# power.net
KiCad netlist of a schematic drawn in Altium Designer
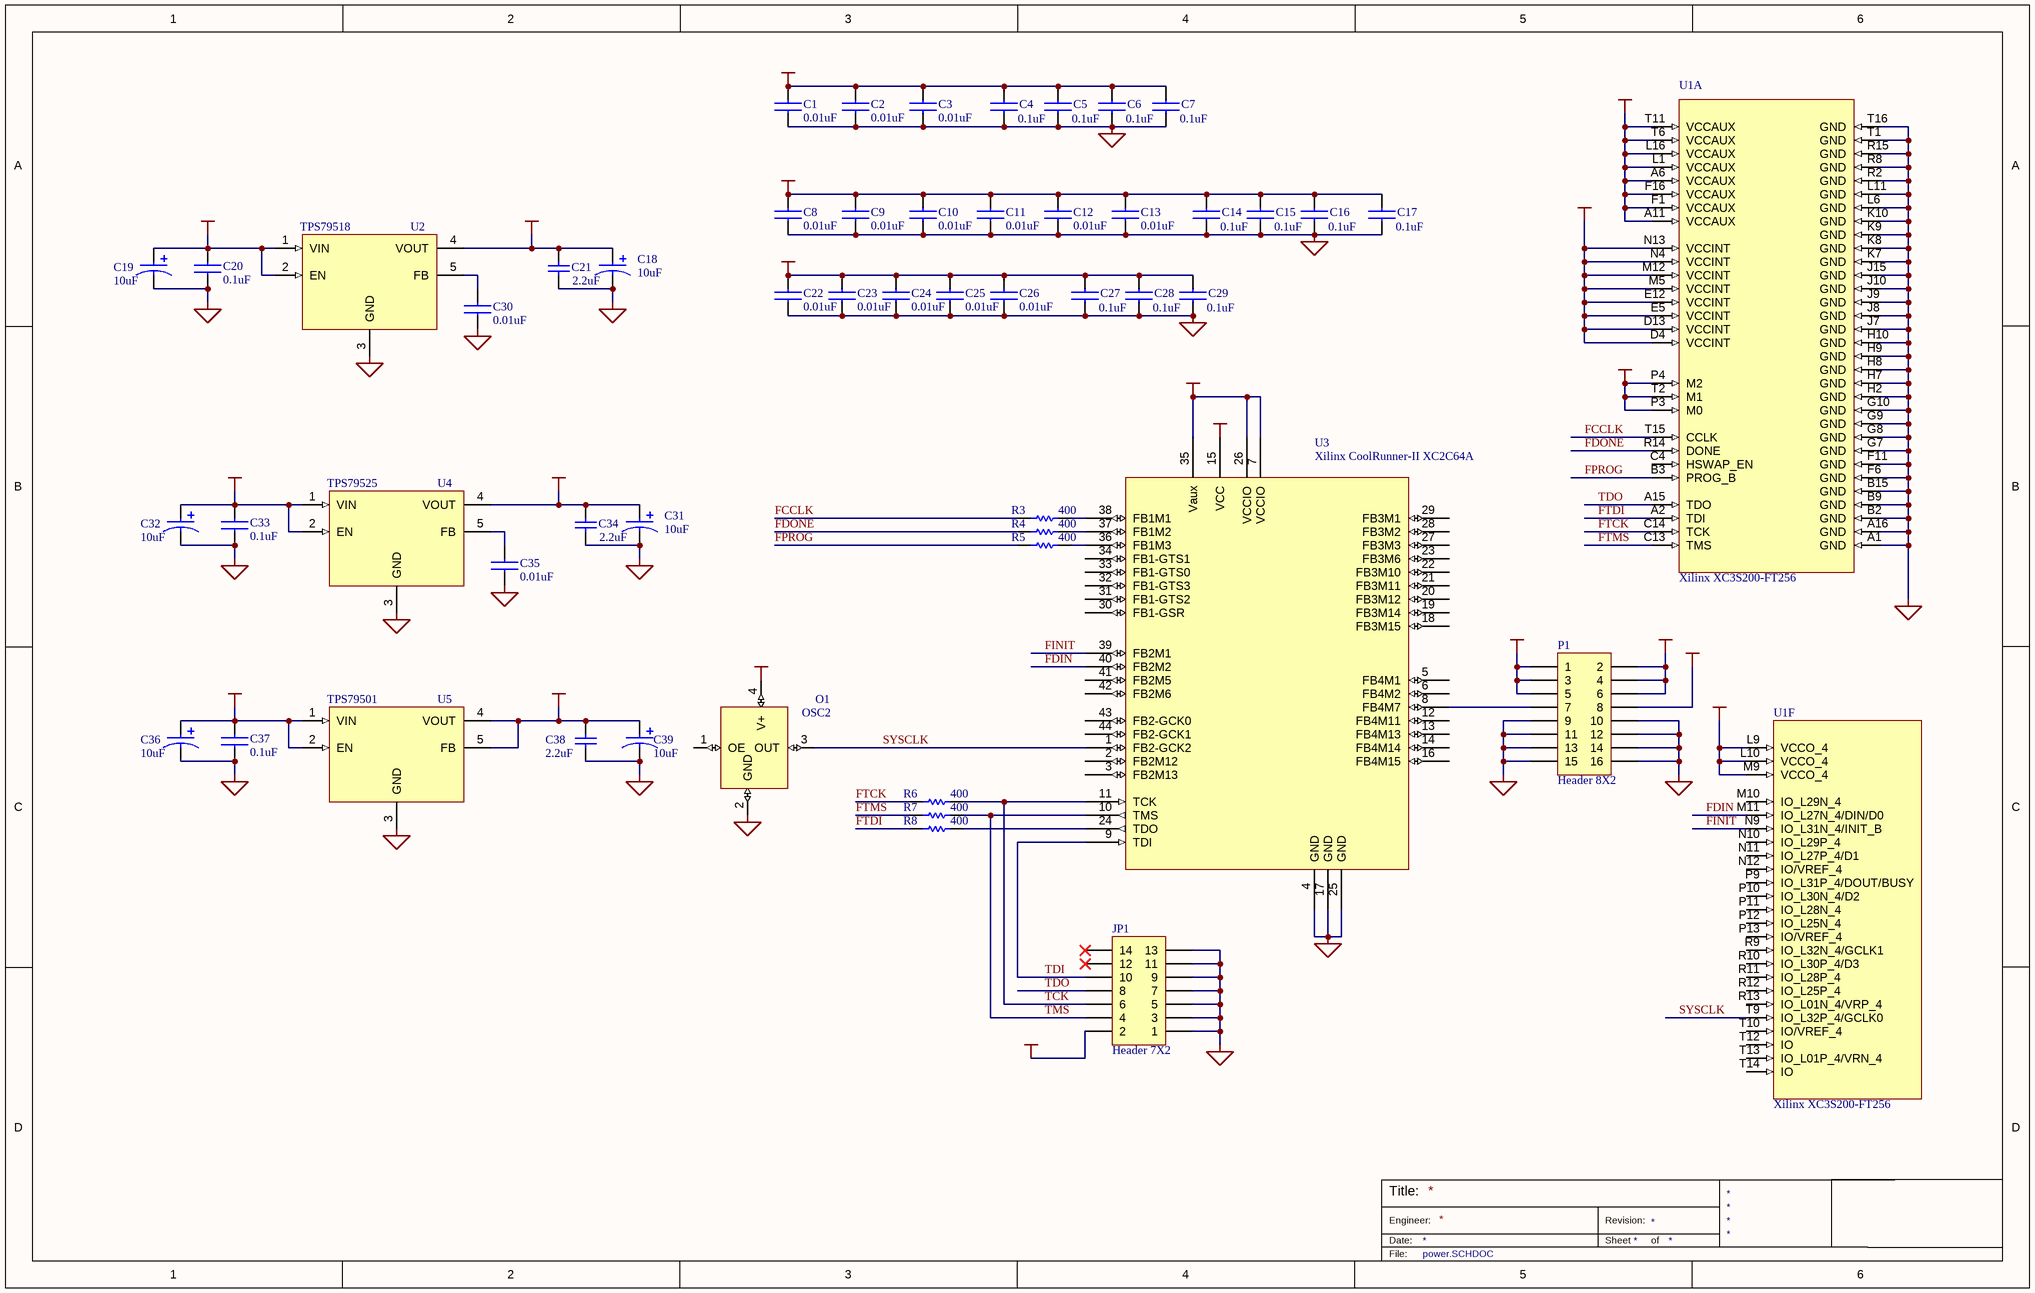
[diagram p0: power.SCHDOC]

(export (version "E")
  (design (tool "Eeschema 10.0.6"))
  (components
    (comp (ref "C1")
      (value "0.01uF")
      (footprint "0402")
      (description "Standard Capacitor")
      (fields (field (name "Comment") "CAPACITOR"))
      (libsource (lib "parts") (part "CAPACITOR"))
    )
    (comp (ref "C2")
      (value "0.01uF")
      (footprint "0402")
      (description "Standard Capacitor")
      (fields (field (name "Comment") "CAPACITOR"))
      (libsource (lib "parts") (part "CAPACITOR"))
    )
    (comp (ref "C3")
      (value "0.01uF")
      (footprint "0402")
      (description "Standard Capacitor")
      (fields (field (name "Comment") "CAPACITOR"))
      (libsource (lib "parts") (part "CAPACITOR"))
    )
    (comp (ref "C4")
      (value "0.1uF")
      (footprint "0603")
      (description "Standard Capacitor")
      (fields (field (name "Comment") "CAPACITOR"))
      (libsource (lib "parts") (part "CAPACITOR"))
    )
    (comp (ref "C5")
      (value "0.1uF")
      (footprint "0603")
      (description "Standard Capacitor")
      (fields (field (name "Comment") "CAPACITOR"))
      (libsource (lib "parts") (part "CAPACITOR"))
    )
    (comp (ref "C6")
      (value "0.1uF")
      (footprint "0603")
      (description "Standard Capacitor")
      (fields (field (name "Comment") "CAPACITOR"))
      (libsource (lib "parts") (part "CAPACITOR"))
    )
    (comp (ref "C7")
      (value "0.1uF")
      (footprint "0603")
      (description "Standard Capacitor")
      (fields (field (name "Comment") "CAPACITOR"))
      (libsource (lib "parts") (part "CAPACITOR"))
    )
    (comp (ref "C8")
      (value "0.01uF")
      (footprint "0402")
      (description "Standard Capacitor")
      (fields (field (name "Comment") "CAPACITOR"))
      (libsource (lib "parts") (part "CAPACITOR"))
    )
    (comp (ref "C9")
      (value "0.01uF")
      (footprint "0402")
      (description "Standard Capacitor")
      (fields (field (name "Comment") "CAPACITOR"))
      (libsource (lib "parts") (part "CAPACITOR"))
    )
    (comp (ref "C10")
      (value "0.01uF")
      (footprint "0402")
      (description "Standard Capacitor")
      (fields (field (name "Comment") "CAPACITOR"))
      (libsource (lib "parts") (part "CAPACITOR"))
    )
    (comp (ref "C11")
      (value "0.01uF")
      (footprint "0402")
      (description "Standard Capacitor")
      (fields (field (name "Comment") "CAPACITOR"))
      (libsource (lib "parts") (part "CAPACITOR"))
    )
    (comp (ref "C12")
      (value "0.01uF")
      (footprint "0402")
      (description "Standard Capacitor")
      (fields (field (name "Comment") "CAPACITOR"))
      (libsource (lib "parts") (part "CAPACITOR"))
    )
    (comp (ref "C13")
      (value "0.01uF")
      (footprint "0402")
      (description "Standard Capacitor")
      (fields (field (name "Comment") "CAPACITOR"))
      (libsource (lib "parts") (part "CAPACITOR"))
    )
    (comp (ref "C14")
      (value "0.1uF")
      (footprint "0603")
      (description "Standard Capacitor")
      (fields (field (name "Comment") "CAPACITOR"))
      (libsource (lib "parts") (part "CAPACITOR"))
    )
    (comp (ref "C15")
      (value "0.1uF")
      (footprint "0603")
      (description "Standard Capacitor")
      (fields (field (name "Comment") "CAPACITOR"))
      (libsource (lib "parts") (part "CAPACITOR"))
    )
    (comp (ref "C16")
      (value "0.1uF")
      (footprint "0603")
      (description "Standard Capacitor")
      (fields (field (name "Comment") "CAPACITOR"))
      (libsource (lib "parts") (part "CAPACITOR"))
    )
    (comp (ref "C17")
      (value "0.1uF")
      (footprint "0603")
      (description "Standard Capacitor")
      (fields (field (name "Comment") "CAPACITOR"))
      (libsource (lib "parts") (part "CAPACITOR"))
    )
    (comp (ref "C18")
      (value "10uF")
      (footprint "6032")
      (description "Standard Capacitor")
      (fields (field (name "Comment") "POLCAP2"))
      (libsource (lib "parts") (part "POLCAP2"))
    )
    (comp (ref "C19")
      (value "10uF")
      (footprint "6032")
      (description "Standard Capacitor")
      (fields (field (name "Comment") "POLCAP2"))
      (libsource (lib "parts") (part "POLCAP2"))
    )
    (comp (ref "C20")
      (value "0.1uF")
      (footprint "0603")
      (description "Standard Capacitor")
      (fields (field (name "Comment") "CAPACITOR"))
      (libsource (lib "parts") (part "CAPACITOR"))
    )
    (comp (ref "C21")
      (value "2.2uF")
      (footprint "1206")
      (description "Capacitor")
      (fields
        (field (name "MANUFACTURER") "Generic Components")
        (field (name "Comment") "Cap")
        (field (name "PUBLISHER") "Altium Limited")
      )
      (libsource (lib "Miscellaneous Devices") (part "Cap"))
    )
    (comp (ref "C22")
      (value "0.01uF")
      (footprint "0402")
      (description "Standard Capacitor")
      (fields (field (name "Comment") "CAPACITOR"))
      (libsource (lib "parts") (part "CAPACITOR"))
    )
    (comp (ref "C23")
      (value "0.01uF")
      (footprint "0402")
      (description "Standard Capacitor")
      (fields (field (name "Comment") "CAPACITOR"))
      (libsource (lib "parts") (part "CAPACITOR"))
    )
    (comp (ref "C24")
      (value "0.01uF")
      (footprint "0402")
      (description "Standard Capacitor")
      (fields (field (name "Comment") "CAPACITOR"))
      (libsource (lib "parts") (part "CAPACITOR"))
    )
    (comp (ref "C25")
      (value "0.01uF")
      (footprint "0402")
      (description "Standard Capacitor")
      (fields (field (name "Comment") "CAPACITOR"))
      (libsource (lib "parts") (part "CAPACITOR"))
    )
    (comp (ref "C26")
      (value "0.01uF")
      (footprint "0402")
      (description "Standard Capacitor")
      (fields (field (name "Comment") "CAPACITOR"))
      (libsource (lib "parts") (part "CAPACITOR"))
    )
    (comp (ref "C27")
      (value "0.1uF")
      (footprint "0603")
      (description "Standard Capacitor")
      (fields (field (name "Comment") "CAPACITOR"))
      (libsource (lib "parts") (part "CAPACITOR"))
    )
    (comp (ref "C28")
      (value "0.1uF")
      (footprint "0603")
      (description "Standard Capacitor")
      (fields (field (name "Comment") "CAPACITOR"))
      (libsource (lib "parts") (part "CAPACITOR"))
    )
    (comp (ref "C29")
      (value "0.1uF")
      (footprint "0603")
      (description "Standard Capacitor")
      (fields (field (name "Comment") "CAPACITOR"))
      (libsource (lib "parts") (part "CAPACITOR"))
    )
    (comp (ref "C30")
      (value "0.01uF")
      (footprint "0402")
      (description "Standard Capacitor")
      (fields (field (name "Comment") "CAPACITOR"))
      (libsource (lib "parts") (part "CAPACITOR"))
    )
    (comp (ref "C31")
      (value "10uF")
      (footprint "6032")
      (description "Standard Capacitor")
      (fields (field (name "Comment") "POLCAP2"))
      (libsource (lib "parts") (part "POLCAP2"))
    )
    (comp (ref "C32")
      (value "10uF")
      (footprint "6032")
      (description "Standard Capacitor")
      (fields (field (name "Comment") "POLCAP2"))
      (libsource (lib "parts") (part "POLCAP2"))
    )
    (comp (ref "C33")
      (value "0.1uF")
      (footprint "0603")
      (description "Standard Capacitor")
      (fields (field (name "Comment") "CAPACITOR"))
      (libsource (lib "parts") (part "CAPACITOR"))
    )
    (comp (ref "C34")
      (value "2.2uF")
      (footprint "1206")
      (description "Capacitor")
      (fields
        (field (name "MANUFACTURER") "Generic Components")
        (field (name "Comment") "Cap")
        (field (name "PUBLISHER") "Altium Limited")
      )
      (libsource (lib "Miscellaneous Devices") (part "Cap"))
    )
    (comp (ref "C35")
      (value "0.01uF")
      (footprint "0402")
      (description "Standard Capacitor")
      (fields (field (name "Comment") "CAPACITOR"))
      (libsource (lib "parts") (part "CAPACITOR"))
    )
    (comp (ref "C36")
      (value "10uF")
      (footprint "6032")
      (description "Standard Capacitor")
      (fields (field (name "Comment") "POLCAP2"))
      (libsource (lib "parts") (part "POLCAP2"))
    )
    (comp (ref "C37")
      (value "0.1uF")
      (footprint "0603")
      (description "Standard Capacitor")
      (fields (field (name "Comment") "CAPACITOR"))
      (libsource (lib "parts") (part "CAPACITOR"))
    )
    (comp (ref "C38")
      (value "2.2uF")
      (footprint "1206")
      (description "Capacitor")
      (fields
        (field (name "MANUFACTURER") "Generic Components")
        (field (name "Comment") "Cap")
        (field (name "PUBLISHER") "Altium Limited")
      )
      (libsource (lib "Miscellaneous Devices") (part "Cap"))
    )
    (comp (ref "C39")
      (value "10uF")
      (footprint "6032")
      (description "Standard Capacitor")
      (fields (field (name "Comment") "POLCAP2"))
      (libsource (lib "parts") (part "POLCAP2"))
    )
    (comp (ref "JP1")
      (value "Header 7X2")
      (footprint "SMT 2x7 2mm HDR")
      (description "Header, 7-Pin, Dual row")
      (fields (field (name "MANUFACTURER") "Generic Components") (field (name "PUBLISHER") "Altium Limited"))
      (libsource (lib "Miscellaneous Connectors") (part "Header 7X2"))
    )
    (comp (ref "O1")
      (value "OSC2")
      (footprint "ECS-3953M")
      (description "ECS SMD Oscillator, ECS-3953M")
      (libsource (lib "parts") (part "OSC2"))
    )
    (comp (ref "P1")
      (value "Header 8X2")
      (footprint "MOLEX 15-91-2160")
      (description "Header, 8-Pin, Dual row")
      (fields (field (name "PUBLISHER") "Altium Limited"))
      (libsource (lib "Miscellaneous Connectors") (part "Header 8X2"))
    )
    (comp (ref "R3")
      (value "400")
      (footprint "CC1608-0603")
      (description "Resistor")
      (fields
        (field (name "MANUFACTURER") "Generic Components")
        (field (name "Comment") "current-limiting series res")
        (field (name "PUBLISHER") "Altium Limited")
      )
      (libsource (lib "Miscellaneous Devices") (part "Res1"))
    )
    (comp (ref "R4")
      (value "400")
      (footprint "CC1608-0603")
      (description "Resistor")
      (fields
        (field (name "MANUFACTURER") "Generic Components")
        (field (name "Comment") "current-limiting series res")
        (field (name "PUBLISHER") "Altium Limited")
      )
      (libsource (lib "Miscellaneous Devices") (part "Res1"))
    )
    (comp (ref "R5")
      (value "400")
      (footprint "CC1608-0603")
      (description "Resistor")
      (fields
        (field (name "MANUFACTURER") "Generic Components")
        (field (name "Comment") "current-limiting series res")
        (field (name "PUBLISHER") "Altium Limited")
      )
      (libsource (lib "Miscellaneous Devices") (part "Res1"))
    )
    (comp (ref "R6")
      (value "400")
      (footprint "CC1608-0603")
      (description "Resistor")
      (fields
        (field (name "MANUFACTURER") "Generic Components")
        (field (name "Comment") "current-limiting series res")
        (field (name "PUBLISHER") "Altium Limited")
      )
      (libsource (lib "Miscellaneous Devices") (part "Res1"))
    )
    (comp (ref "R7")
      (value "400")
      (footprint "CC1608-0603")
      (description "Resistor")
      (fields
        (field (name "MANUFACTURER") "Generic Components")
        (field (name "Comment") "current-limiting series res")
        (field (name "PUBLISHER") "Altium Limited")
      )
      (libsource (lib "Miscellaneous Devices") (part "Res1"))
    )
    (comp (ref "R8")
      (value "400")
      (footprint "CC1608-0603")
      (description "Resistor")
      (fields
        (field (name "MANUFACTURER") "Generic Components")
        (field (name "Comment") "current-limiting series res")
        (field (name "PUBLISHER") "Altium Limited")
      )
      (libsource (lib "Miscellaneous Devices") (part "Res1"))
    )
    (comp (ref "U1")
      (value "Xilinx XC3S200-FT256")
      (footprint "Xilinx FT256 BGA")
      (description "Xilinx Spartan-3 FPGA")
      (libsource (lib "") (part "XC3S200-FT256_1"))
    )
    (comp (ref "U2")
      (value "TPS79518")
      (footprint "SOT223-5/Simple")
      (description "TI Ultra-low-noise LDO")
      (libsource (lib "parts") (part "TPS795XX"))
    )
    (comp (ref "U3")
      (value "Xilinx CoolRunner-II XC2C64A")
      (footprint "QFP10x10-G44/G10N")
      (libsource (lib "parts") (part "XC2C64A-5VQ44C"))
    )
    (comp (ref "U4")
      (value "TPS79525")
      (footprint "SOT223-5/Simple")
      (description "TI Ultra-low-noise LDO")
      (libsource (lib "parts") (part "TPS795XX"))
    )
    (comp (ref "U5")
      (value "TPS79501")
      (footprint "SOT223-5/Simple")
      (description "TI Ultra-low-noise LDO")
      (libsource (lib "parts") (part "TPS795XX"))
    )
  )
  (nets
    (net (code "1") (name "+1.2VCC") (class "Default")
      (node (ref "C1") (pin "1") (pintype "passive"))
      (node (ref "C2") (pin "1") (pintype "passive"))
      (node (ref "C3") (pin "1") (pintype "passive"))
      (node (ref "C38") (pin "2") (pinfunction "2_2") (pintype "passive"))
      (node (ref "C39") (pin "1") (pintype "passive"))
      (node (ref "C4") (pin "1") (pintype "passive"))
      (node (ref "C5") (pin "1") (pintype "passive"))
      (node (ref "C6") (pin "1") (pintype "passive"))
      (node (ref "C7") (pin "1") (pintype "passive"))
      (node (ref "U1") (pin "D13") (pinfunction "VCCINT_D13") (pintype "input"))
      (node (ref "U1") (pin "D4") (pinfunction "VCCINT_D4") (pintype "input"))
      (node (ref "U1") (pin "E12") (pinfunction "VCCINT_E12") (pintype "input"))
      (node (ref "U1") (pin "E5") (pinfunction "VCCINT_E5") (pintype "input"))
      (node (ref "U1") (pin "M12") (pinfunction "VCCINT_M12") (pintype "input"))
      (node (ref "U1") (pin "M5") (pinfunction "VCCINT_M5") (pintype "input"))
      (node (ref "U1") (pin "N13") (pinfunction "VCCINT_N13") (pintype "input"))
      (node (ref "U1") (pin "N4") (pinfunction "VCCINT_N4") (pintype "input"))
      (node (ref "U5") (pin "4") (pinfunction "VOUT_4") (pintype "power_in"))
      (node (ref "U5") (pin "5") (pinfunction "FB_5") (pintype "passive"))
    )
    (net (code "2") (name "+1.8VCC") (class "Default")
      (node (ref "C18") (pin "1") (pintype "passive"))
      (node (ref "C21") (pin "2") (pinfunction "2_2") (pintype "passive"))
      (node (ref "U2") (pin "4") (pinfunction "VOUT_4") (pintype "power_in"))
      (node (ref "U3") (pin "15") (pinfunction "VCC_15") (pintype "power_in"))
    )
    (net (code "3") (name "+2.5VCC") (class "Default")
      (node (ref "C10") (pin "1") (pintype "passive"))
      (node (ref "C11") (pin "1") (pintype "passive"))
      (node (ref "C12") (pin "1") (pintype "passive"))
      (node (ref "C13") (pin "1") (pintype "passive"))
      (node (ref "C14") (pin "1") (pintype "passive"))
      (node (ref "C15") (pin "1") (pintype "passive"))
      (node (ref "C16") (pin "1") (pintype "passive"))
      (node (ref "C17") (pin "1") (pintype "passive"))
      (node (ref "C31") (pin "1") (pintype "passive"))
      (node (ref "C34") (pin "2") (pinfunction "2_2") (pintype "passive"))
      (node (ref "C8") (pin "1") (pintype "passive"))
      (node (ref "C9") (pin "1") (pintype "passive"))
      (node (ref "U1") (pin "A11") (pinfunction "VCCAUX_A11") (pintype "input"))
      (node (ref "U1") (pin "A6") (pinfunction "VCCAUX_A6") (pintype "input"))
      (node (ref "U1") (pin "F1") (pinfunction "VCCAUX_F1") (pintype "input"))
      (node (ref "U1") (pin "F16") (pinfunction "VCCAUX_F16") (pintype "input"))
      (node (ref "U1") (pin "L1") (pinfunction "VCCAUX_L1") (pintype "input"))
      (node (ref "U1") (pin "L16") (pinfunction "VCCAUX_L16") (pintype "input"))
      (node (ref "U1") (pin "T11") (pinfunction "VCCAUX_T11") (pintype "input"))
      (node (ref "U1") (pin "T6") (pinfunction "VCCAUX_T6") (pintype "input"))
      (node (ref "U4") (pin "4") (pinfunction "VOUT_4") (pintype "power_in"))
    )
    (net (code "4") (name "+5VCC") (class "Default")
      (node (ref "P1") (pin "2") (pinfunction "2_2") (pintype "passive"))
      (node (ref "P1") (pin "4") (pinfunction "4_4") (pintype "passive"))
      (node (ref "P1") (pin "6") (pinfunction "6_6") (pintype "passive"))
    )
    (net (code "5") (name "+12VCC") (class "Default")
      (node (ref "P1") (pin "8") (pinfunction "8_8") (pintype "passive"))
    )
    (net (code "6") (name "/FCCLK") (class "Default")
      (node (ref "R3") (pin "2") (pinfunction "2_2") (pintype "passive"))
      (node (ref "U1") (pin "T15") (pinfunction "CCLK_T15") (pintype "input"))
    )
    (net (code "7") (name "/FDIN") (class "Default")
      (node (ref "U1") (pin "M11") (pinfunction "IO_L27N_4/DIN/D0_M11") (pintype "input"))
      (node (ref "U3") (pin "40") (pinfunction "FB2M2_40") (pintype "bidirectional"))
    )
    (net (code "8") (name "/FDONE") (class "Default")
      (node (ref "R4") (pin "2") (pinfunction "2_2") (pintype "passive"))
      (node (ref "U1") (pin "R14") (pinfunction "DONE_R14") (pintype "input"))
    )
    (net (code "9") (name "/FINIT") (class "Default")
      (node (ref "U1") (pin "N9") (pinfunction "IO_L31N_4/INIT_B_N9") (pintype "input"))
      (node (ref "U3") (pin "39") (pinfunction "FB2M1_39") (pintype "bidirectional"))
    )
    (net (code "10") (name "/FPROG") (class "Default")
      (node (ref "R5") (pin "2") (pinfunction "2_2") (pintype "passive"))
      (node (ref "U1") (pin "B3") (pinfunction "PROG_B_B3") (pintype "input"))
    )
    (net (code "11") (name "/FTCK") (class "Default")
      (node (ref "R6") (pin "2") (pinfunction "2_2") (pintype "passive"))
      (node (ref "U1") (pin "C14") (pinfunction "TCK_C14") (pintype "input"))
    )
    (net (code "12") (name "/FTDI") (class "Default")
      (node (ref "R8") (pin "2") (pinfunction "2_2") (pintype "passive"))
      (node (ref "U1") (pin "A2") (pinfunction "TDI_A2") (pintype "input"))
    )
    (net (code "13") (name "/FTMS") (class "Default")
      (node (ref "R7") (pin "1") (pinfunction "1_1") (pintype "passive"))
      (node (ref "U1") (pin "C13") (pinfunction "TMS_C13") (pintype "input"))
    )
    (net (code "14") (name "/SYSCLK") (class "Default")
      (node (ref "O1") (pin "3") (pinfunction "OUT_3") (pintype "bidirectional"))
      (node (ref "U1") (pin "T9") (pinfunction "IO_L32P_4/GCLK0_T9") (pintype "input"))
      (node (ref "U3") (pin "1") (pinfunction "FB2-GCK2_1") (pintype "bidirectional"))
    )
    (net (code "15") (name "/TCK") (class "Default")
      (node (ref "JP1") (pin "6") (pinfunction "6_6") (pintype "passive"))
      (node (ref "R6") (pin "1") (pinfunction "1_1") (pintype "passive"))
      (node (ref "U3") (pin "11") (pinfunction "TCK_11") (pintype "input"))
    )
    (net (code "16") (name "/TDI") (class "Default")
      (node (ref "JP1") (pin "10") (pinfunction "10_10") (pintype "passive"))
      (node (ref "U3") (pin "9") (pinfunction "TDI_9") (pintype "input"))
    )
    (net (code "17") (name "/TDO") (class "Default")
      (node (ref "JP1") (pin "8") (pinfunction "8_8") (pintype "passive"))
      (node (ref "U1") (pin "A15") (pinfunction "TDO_A15") (pintype "input"))
    )
    (net (code "18") (name "/TMS") (class "Default")
      (node (ref "JP1") (pin "4") (pinfunction "4_4") (pintype "passive"))
      (node (ref "R7") (pin "2") (pinfunction "2_2") (pintype "passive"))
      (node (ref "U3") (pin "10") (pinfunction "TMS_10") (pintype "output"))
    )
    (net (code "19") (name "GND") (class "Default")
      (node (ref "C1") (pin "2") (pintype "passive"))
      (node (ref "C10") (pin "2") (pintype "passive"))
      (node (ref "C11") (pin "2") (pintype "passive"))
      (node (ref "C12") (pin "2") (pintype "passive"))
      (node (ref "C13") (pin "2") (pintype "passive"))
      (node (ref "C14") (pin "2") (pintype "passive"))
      (node (ref "C15") (pin "2") (pintype "passive"))
      (node (ref "C16") (pin "2") (pintype "passive"))
      (node (ref "C17") (pin "2") (pintype "passive"))
      (node (ref "C18") (pin "2") (pintype "passive"))
      (node (ref "C19") (pin "2") (pintype "passive"))
      (node (ref "C2") (pin "2") (pintype "passive"))
      (node (ref "C20") (pin "1") (pintype "passive"))
      (node (ref "C21") (pin "1") (pinfunction "1_1") (pintype "passive"))
      (node (ref "C22") (pin "2") (pintype "passive"))
      (node (ref "C23") (pin "2") (pintype "passive"))
      (node (ref "C24") (pin "2") (pintype "passive"))
      (node (ref "C25") (pin "2") (pintype "passive"))
      (node (ref "C26") (pin "2") (pintype "passive"))
      (node (ref "C27") (pin "2") (pintype "passive"))
      (node (ref "C28") (pin "2") (pintype "passive"))
      (node (ref "C29") (pin "2") (pintype "passive"))
      (node (ref "C3") (pin "2") (pintype "passive"))
      (node (ref "C30") (pin "1") (pintype "passive"))
      (node (ref "C31") (pin "2") (pintype "passive"))
      (node (ref "C32") (pin "2") (pintype "passive"))
      (node (ref "C33") (pin "1") (pintype "passive"))
      (node (ref "C34") (pin "1") (pinfunction "1_1") (pintype "passive"))
      (node (ref "C35") (pin "1") (pintype "passive"))
      (node (ref "C36") (pin "2") (pintype "passive"))
      (node (ref "C37") (pin "1") (pintype "passive"))
      (node (ref "C38") (pin "1") (pinfunction "1_1") (pintype "passive"))
      (node (ref "C39") (pin "2") (pintype "passive"))
      (node (ref "C4") (pin "2") (pintype "passive"))
      (node (ref "C5") (pin "2") (pintype "passive"))
      (node (ref "C6") (pin "2") (pintype "passive"))
      (node (ref "C7") (pin "2") (pintype "passive"))
      (node (ref "C8") (pin "2") (pintype "passive"))
      (node (ref "C9") (pin "2") (pintype "passive"))
      (node (ref "JP1") (pin "1") (pinfunction "1_1") (pintype "passive"))
      (node (ref "JP1") (pin "11") (pinfunction "11_11") (pintype "passive"))
      (node (ref "JP1") (pin "13") (pinfunction "13_13") (pintype "passive"))
      (node (ref "JP1") (pin "3") (pinfunction "3_3") (pintype "passive"))
      (node (ref "JP1") (pin "5") (pinfunction "5_5") (pintype "passive"))
      (node (ref "JP1") (pin "7") (pinfunction "7_7") (pintype "passive"))
      (node (ref "JP1") (pin "9") (pinfunction "9_9") (pintype "passive"))
      (node (ref "O1") (pin "2") (pinfunction "GND_2") (pintype "bidirectional"))
      (node (ref "P1") (pin "10") (pinfunction "10_10") (pintype "passive"))
      (node (ref "P1") (pin "11") (pinfunction "11_11") (pintype "passive"))
      (node (ref "P1") (pin "12") (pinfunction "12_12") (pintype "passive"))
      (node (ref "P1") (pin "13") (pinfunction "13_13") (pintype "passive"))
      (node (ref "P1") (pin "14") (pinfunction "14_14") (pintype "passive"))
      (node (ref "P1") (pin "15") (pinfunction "15_15") (pintype "passive"))
      (node (ref "P1") (pin "16") (pinfunction "16_16") (pintype "passive"))
      (node (ref "P1") (pin "9") (pinfunction "9_9") (pintype "passive"))
      (node (ref "U1") (pin "A1") (pinfunction "GND_A1") (pintype "input"))
      (node (ref "U1") (pin "A16") (pinfunction "GND_A16") (pintype "input"))
      (node (ref "U1") (pin "B15") (pinfunction "GND_B15") (pintype "input"))
      (node (ref "U1") (pin "B2") (pinfunction "GND_B2") (pintype "input"))
      (node (ref "U1") (pin "B9") (pinfunction "GND_B9") (pintype "input"))
      (node (ref "U1") (pin "F11") (pinfunction "GND_F11") (pintype "input"))
      (node (ref "U1") (pin "F6") (pinfunction "GND_F6") (pintype "input"))
      (node (ref "U1") (pin "G10") (pinfunction "GND_G10") (pintype "input"))
      (node (ref "U1") (pin "G7") (pinfunction "GND_G7") (pintype "input"))
      (node (ref "U1") (pin "G8") (pinfunction "GND_G8") (pintype "input"))
      (node (ref "U1") (pin "G9") (pinfunction "GND_G9") (pintype "input"))
      (node (ref "U1") (pin "H10") (pinfunction "GND_H10") (pintype "input"))
      (node (ref "U1") (pin "H2") (pinfunction "GND_H2") (pintype "input"))
      (node (ref "U1") (pin "H7") (pinfunction "GND_H7") (pintype "input"))
      (node (ref "U1") (pin "H8") (pinfunction "GND_H8") (pintype "input"))
      (node (ref "U1") (pin "H9") (pinfunction "GND_H9") (pintype "input"))
      (node (ref "U1") (pin "J10") (pinfunction "GND_J10") (pintype "input"))
      (node (ref "U1") (pin "J15") (pinfunction "GND_J15") (pintype "input"))
      (node (ref "U1") (pin "J7") (pinfunction "GND_J7") (pintype "input"))
      (node (ref "U1") (pin "J8") (pinfunction "GND_J8") (pintype "input"))
      (node (ref "U1") (pin "J9") (pinfunction "GND_J9") (pintype "input"))
      (node (ref "U1") (pin "K10") (pinfunction "GND_K10") (pintype "input"))
      (node (ref "U1") (pin "K7") (pinfunction "GND_K7") (pintype "input"))
      (node (ref "U1") (pin "K8") (pinfunction "GND_K8") (pintype "input"))
      (node (ref "U1") (pin "K9") (pinfunction "GND_K9") (pintype "input"))
      (node (ref "U1") (pin "L11") (pinfunction "GND_L11") (pintype "input"))
      (node (ref "U1") (pin "L6") (pinfunction "GND_L6") (pintype "input"))
      (node (ref "U1") (pin "R15") (pinfunction "GND_R15") (pintype "input"))
      (node (ref "U1") (pin "R2") (pinfunction "GND_R2") (pintype "input"))
      (node (ref "U1") (pin "R8") (pinfunction "GND_R8") (pintype "input"))
      (node (ref "U1") (pin "T1") (pinfunction "GND_T1") (pintype "input"))
      (node (ref "U1") (pin "T16") (pinfunction "GND_T16") (pintype "input"))
      (node (ref "U2") (pin "3") (pinfunction "GND_3") (pintype "power_in"))
      (node (ref "U3") (pin "17") (pinfunction "GND_17") (pintype "power_in"))
      (node (ref "U3") (pin "25") (pinfunction "GND_25") (pintype "power_in"))
      (node (ref "U3") (pin "4") (pinfunction "GND_4") (pintype "power_in"))
      (node (ref "U4") (pin "3") (pinfunction "GND_3") (pintype "power_in"))
      (node (ref "U5") (pin "3") (pinfunction "GND_3") (pintype "power_in"))
    )
    (net (code "20") (name "Net-(U2-FB)") (class "Default")
      (node (ref "C30") (pin "2") (pintype "passive"))
      (node (ref "U2") (pin "5") (pinfunction "FB_5") (pintype "passive"))
    )
    (net (code "21") (name "Net-(U3-FB1M1)") (class "Default")
      (node (ref "R3") (pin "1") (pinfunction "1_1") (pintype "passive"))
      (node (ref "U3") (pin "38") (pinfunction "FB1M1_38") (pintype "bidirectional"))
    )
    (net (code "22") (name "Net-(U3-FB1M2)") (class "Default")
      (node (ref "R4") (pin "1") (pinfunction "1_1") (pintype "passive"))
      (node (ref "U3") (pin "37") (pinfunction "FB1M2_37") (pintype "bidirectional"))
    )
    (net (code "23") (name "Net-(U3-FB1M3)") (class "Default")
      (node (ref "R5") (pin "1") (pinfunction "1_1") (pintype "passive"))
      (node (ref "U3") (pin "36") (pinfunction "FB1M3_36") (pintype "bidirectional"))
    )
    (net (code "24") (name "Net-(U3-FB4M7)") (class "Default")
      (node (ref "P1") (pin "7") (pinfunction "7_7") (pintype "passive"))
      (node (ref "U3") (pin "8") (pinfunction "FB4M7_8") (pintype "bidirectional"))
    )
    (net (code "25") (name "Net-(U3-TDO)") (class "Default")
      (node (ref "R8") (pin "1") (pinfunction "1_1") (pintype "passive"))
      (node (ref "U3") (pin "24") (pinfunction "TDO_24") (pintype "output"))
    )
    (net (code "26") (name "Net-(U4-FB)") (class "Default")
      (node (ref "C35") (pin "2") (pintype "passive"))
      (node (ref "U4") (pin "5") (pinfunction "FB_5") (pintype "passive"))
    )
    (net (code "27") (name "VCC") (class "Default")
      (node (ref "C19") (pin "1") (pintype "passive"))
      (node (ref "C20") (pin "2") (pintype "passive"))
      (node (ref "C22") (pin "1") (pintype "passive"))
      (node (ref "C23") (pin "1") (pintype "passive"))
      (node (ref "C24") (pin "1") (pintype "passive"))
      (node (ref "C25") (pin "1") (pintype "passive"))
      (node (ref "C26") (pin "1") (pintype "passive"))
      (node (ref "C27") (pin "1") (pintype "passive"))
      (node (ref "C28") (pin "1") (pintype "passive"))
      (node (ref "C29") (pin "1") (pintype "passive"))
      (node (ref "C32") (pin "1") (pintype "passive"))
      (node (ref "C33") (pin "2") (pintype "passive"))
      (node (ref "C36") (pin "1") (pintype "passive"))
      (node (ref "C37") (pin "2") (pintype "passive"))
      (node (ref "JP1") (pin "2") (pinfunction "2_2") (pintype "passive"))
      (node (ref "O1") (pin "4") (pinfunction "V+_4") (pintype "bidirectional"))
      (node (ref "P1") (pin "1") (pinfunction "1_1") (pintype "passive"))
      (node (ref "P1") (pin "3") (pinfunction "3_3") (pintype "passive"))
      (node (ref "P1") (pin "5") (pinfunction "5_5") (pintype "passive"))
      (node (ref "U1") (pin "L10") (pinfunction "VCCO_4_L10") (pintype "input"))
      (node (ref "U1") (pin "L9") (pinfunction "VCCO_4_L9") (pintype "input"))
      (node (ref "U1") (pin "M9") (pinfunction "VCCO_4_M9") (pintype "input"))
      (node (ref "U1") (pin "P3") (pinfunction "M0_P3") (pintype "input"))
      (node (ref "U1") (pin "P4") (pinfunction "M2_P4") (pintype "input"))
      (node (ref "U1") (pin "T2") (pinfunction "M1_T2") (pintype "input"))
      (node (ref "U2") (pin "1") (pinfunction "VIN_1") (pintype "input"))
      (node (ref "U2") (pin "2") (pinfunction "EN_2") (pintype "input"))
      (node (ref "U3") (pin "26") (pinfunction "VCCIO_26") (pintype "power_in"))
      (node (ref "U3") (pin "35") (pinfunction "Vaux_35") (pintype "power_in"))
      (node (ref "U3") (pin "7") (pinfunction "VCCIO_7") (pintype "power_in"))
      (node (ref "U4") (pin "1") (pinfunction "VIN_1") (pintype "input"))
      (node (ref "U4") (pin "2") (pinfunction "EN_2") (pintype "input"))
      (node (ref "U5") (pin "1") (pinfunction "VIN_1") (pintype "input"))
      (node (ref "U5") (pin "2") (pinfunction "EN_2") (pintype "input"))
    )
    (net (code "28") (name "unconnected-(JP1-Pad12)") (class "Default")
      (node (ref "JP1") (pin "12") (pinfunction "12_12") (pintype "passive+no_connect"))
    )
    (net (code "29") (name "unconnected-(JP1-Pad14)") (class "Default")
      (node (ref "JP1") (pin "14") (pinfunction "14_14") (pintype "passive+no_connect"))
    )
    (net (code "30") (name "unconnected-(O1-OE-Pad1)") (class "Default")
      (node (ref "O1") (pin "1") (pinfunction "OE_1") (pintype "bidirectional"))
    )
    (net (code "31") (name "unconnected-(U1A-HSWAP_EN-PadC4)") (class "Default")
      (node (ref "U1") (pin "C4") (pinfunction "HSWAP_EN_C4") (pintype "input"))
    )
    (net (code "32") (name "unconnected-(U1F-IO-PadT12)") (class "Default")
      (node (ref "U1") (pin "T12") (pinfunction "IO_T12") (pintype "input"))
    )
    (net (code "33") (name "unconnected-(U1F-IO-PadT14)") (class "Default")
      (node (ref "U1") (pin "T14") (pinfunction "IO_T14") (pintype "input"))
    )
    (net (code "34") (name "unconnected-(U1F-IO_L01N_4{slash}VRP_4-PadR13)") (class "Default")
      (node (ref "U1") (pin "R13") (pinfunction "IO_L01N_4/VRP_4_R13") (pintype "input"))
    )
    (net (code "35") (name "unconnected-(U1F-IO_L01P_4{slash}VRN_4-PadT13)") (class "Default")
      (node (ref "U1") (pin "T13") (pinfunction "IO_L01P_4/VRN_4_T13") (pintype "input"))
    )
    (net (code "36") (name "unconnected-(U1F-IO_L25N_4-PadP12)") (class "Default")
      (node (ref "U1") (pin "P12") (pinfunction "IO_L25N_4_P12") (pintype "input"))
    )
    (net (code "37") (name "unconnected-(U1F-IO_L25P_4-PadR12)") (class "Default")
      (node (ref "U1") (pin "R12") (pinfunction "IO_L25P_4_R12") (pintype "input"))
    )
    (net (code "38") (name "unconnected-(U1F-IO_L27P_4{slash}D1-PadN11)") (class "Default")
      (node (ref "U1") (pin "N11") (pinfunction "IO_L27P_4/D1_N11") (pintype "input"))
    )
    (net (code "39") (name "unconnected-(U1F-IO_L28N_4-PadP11)") (class "Default")
      (node (ref "U1") (pin "P11") (pinfunction "IO_L28N_4_P11") (pintype "input"))
    )
    (net (code "40") (name "unconnected-(U1F-IO_L28P_4-PadR11)") (class "Default")
      (node (ref "U1") (pin "R11") (pinfunction "IO_L28P_4_R11") (pintype "input"))
    )
    (net (code "41") (name "unconnected-(U1F-IO_L29N_4-PadM10)") (class "Default")
      (node (ref "U1") (pin "M10") (pinfunction "IO_L29N_4_M10") (pintype "input"))
    )
    (net (code "42") (name "unconnected-(U1F-IO_L29P_4-PadN10)") (class "Default")
      (node (ref "U1") (pin "N10") (pinfunction "IO_L29P_4_N10") (pintype "input"))
    )
    (net (code "43") (name "unconnected-(U1F-IO_L30N_4{slash}D2-PadP10)") (class "Default")
      (node (ref "U1") (pin "P10") (pinfunction "IO_L30N_4/D2_P10") (pintype "input"))
    )
    (net (code "44") (name "unconnected-(U1F-IO_L30P_4{slash}D3-PadR10)") (class "Default")
      (node (ref "U1") (pin "R10") (pinfunction "IO_L30P_4/D3_R10") (pintype "input"))
    )
    (net (code "45") (name "unconnected-(U1F-IO_L31P_4{slash}DOUT{slash}BUSY-PadP9)") (class "Default")
      (node (ref "U1") (pin "P9") (pinfunction "IO_L31P_4/DOUT/BUSY_P9") (pintype "input"))
    )
    (net (code "46") (name "unconnected-(U1F-IO_L32N_4{slash}GCLK1-PadR9)") (class "Default")
      (node (ref "U1") (pin "R9") (pinfunction "IO_L32N_4/GCLK1_R9") (pintype "input"))
    )
    (net (code "47") (name "unconnected-(U1F-IO{slash}VREF_4-PadN12)") (class "Default")
      (node (ref "U1") (pin "N12") (pinfunction "IO/VREF_4_N12") (pintype "input"))
    )
    (net (code "48") (name "unconnected-(U1F-IO{slash}VREF_4-PadP13)") (class "Default")
      (node (ref "U1") (pin "P13") (pinfunction "IO/VREF_4_P13") (pintype "input"))
    )
    (net (code "49") (name "unconnected-(U1F-IO{slash}VREF_4-PadT10)") (class "Default")
      (node (ref "U1") (pin "T10") (pinfunction "IO/VREF_4_T10") (pintype "input"))
    )
    (net (code "50") (name "unconnected-(U3-FB1-GSR-Pad30)") (class "Default")
      (node (ref "U3") (pin "30") (pinfunction "FB1-GSR_30") (pintype "bidirectional"))
    )
    (net (code "51") (name "unconnected-(U3-FB1-GTS0-Pad33)") (class "Default")
      (node (ref "U3") (pin "33") (pinfunction "FB1-GTS0_33") (pintype "bidirectional"))
    )
    (net (code "52") (name "unconnected-(U3-FB1-GTS1-Pad34)") (class "Default")
      (node (ref "U3") (pin "34") (pinfunction "FB1-GTS1_34") (pintype "bidirectional"))
    )
    (net (code "53") (name "unconnected-(U3-FB1-GTS2-Pad31)") (class "Default")
      (node (ref "U3") (pin "31") (pinfunction "FB1-GTS2_31") (pintype "bidirectional"))
    )
    (net (code "54") (name "unconnected-(U3-FB1-GTS3-Pad32)") (class "Default")
      (node (ref "U3") (pin "32") (pinfunction "FB1-GTS3_32") (pintype "bidirectional"))
    )
    (net (code "55") (name "unconnected-(U3-FB2-GCK0-Pad43)") (class "Default")
      (node (ref "U3") (pin "43") (pinfunction "FB2-GCK0_43") (pintype "bidirectional"))
    )
    (net (code "56") (name "unconnected-(U3-FB2-GCK1-Pad44)") (class "Default")
      (node (ref "U3") (pin "44") (pinfunction "FB2-GCK1_44") (pintype "bidirectional"))
    )
    (net (code "57") (name "unconnected-(U3-FB2M5-Pad41)") (class "Default")
      (node (ref "U3") (pin "41") (pinfunction "FB2M5_41") (pintype "bidirectional"))
    )
    (net (code "58") (name "unconnected-(U3-FB2M6-Pad42)") (class "Default")
      (node (ref "U3") (pin "42") (pinfunction "FB2M6_42") (pintype "bidirectional"))
    )
    (net (code "59") (name "unconnected-(U3-FB2M12-Pad2)") (class "Default")
      (node (ref "U3") (pin "2") (pinfunction "FB2M12_2") (pintype "bidirectional"))
    )
    (net (code "60") (name "unconnected-(U3-FB2M13-Pad3)") (class "Default")
      (node (ref "U3") (pin "3") (pinfunction "FB2M13_3") (pintype "bidirectional"))
    )
    (net (code "61") (name "unconnected-(U3-FB3M1-Pad29)") (class "Default")
      (node (ref "U3") (pin "29") (pinfunction "FB3M1_29") (pintype "bidirectional"))
    )
    (net (code "62") (name "unconnected-(U3-FB3M2-Pad28)") (class "Default")
      (node (ref "U3") (pin "28") (pinfunction "FB3M2_28") (pintype "bidirectional"))
    )
    (net (code "63") (name "unconnected-(U3-FB3M3-Pad27)") (class "Default")
      (node (ref "U3") (pin "27") (pinfunction "FB3M3_27") (pintype "bidirectional"))
    )
    (net (code "64") (name "unconnected-(U3-FB3M6-Pad23)") (class "Default")
      (node (ref "U3") (pin "23") (pinfunction "FB3M6_23") (pintype "bidirectional"))
    )
    (net (code "65") (name "unconnected-(U3-FB3M10-Pad22)") (class "Default")
      (node (ref "U3") (pin "22") (pinfunction "FB3M10_22") (pintype "bidirectional"))
    )
    (net (code "66") (name "unconnected-(U3-FB3M11-Pad21)") (class "Default")
      (node (ref "U3") (pin "21") (pinfunction "FB3M11_21") (pintype "bidirectional"))
    )
    (net (code "67") (name "unconnected-(U3-FB3M12-Pad20)") (class "Default")
      (node (ref "U3") (pin "20") (pinfunction "FB3M12_20") (pintype "bidirectional"))
    )
    (net (code "68") (name "unconnected-(U3-FB3M14-Pad19)") (class "Default")
      (node (ref "U3") (pin "19") (pinfunction "FB3M14_19") (pintype "bidirectional"))
    )
    (net (code "69") (name "unconnected-(U3-FB3M15-Pad18)") (class "Default")
      (node (ref "U3") (pin "18") (pinfunction "FB3M15_18") (pintype "bidirectional"))
    )
    (net (code "70") (name "unconnected-(U3-FB4M1-Pad5)") (class "Default")
      (node (ref "U3") (pin "5") (pinfunction "FB4M1_5") (pintype "bidirectional"))
    )
    (net (code "71") (name "unconnected-(U3-FB4M2-Pad6)") (class "Default")
      (node (ref "U3") (pin "6") (pinfunction "FB4M2_6") (pintype "bidirectional"))
    )
    (net (code "72") (name "unconnected-(U3-FB4M11-Pad12)") (class "Default")
      (node (ref "U3") (pin "12") (pinfunction "FB4M11_12") (pintype "bidirectional"))
    )
    (net (code "73") (name "unconnected-(U3-FB4M13-Pad13)") (class "Default")
      (node (ref "U3") (pin "13") (pinfunction "FB4M13_13") (pintype "bidirectional"))
    )
    (net (code "74") (name "unconnected-(U3-FB4M14-Pad14)") (class "Default")
      (node (ref "U3") (pin "14") (pinfunction "FB4M14_14") (pintype "bidirectional"))
    )
    (net (code "75") (name "unconnected-(U3-FB4M15-Pad16)") (class "Default")
      (node (ref "U3") (pin "16") (pinfunction "FB4M15_16") (pintype "bidirectional"))
    )
  )
)
